# 07_RAM_PWR.net
KiCad netlist of a schematic drawn in Altium Designer
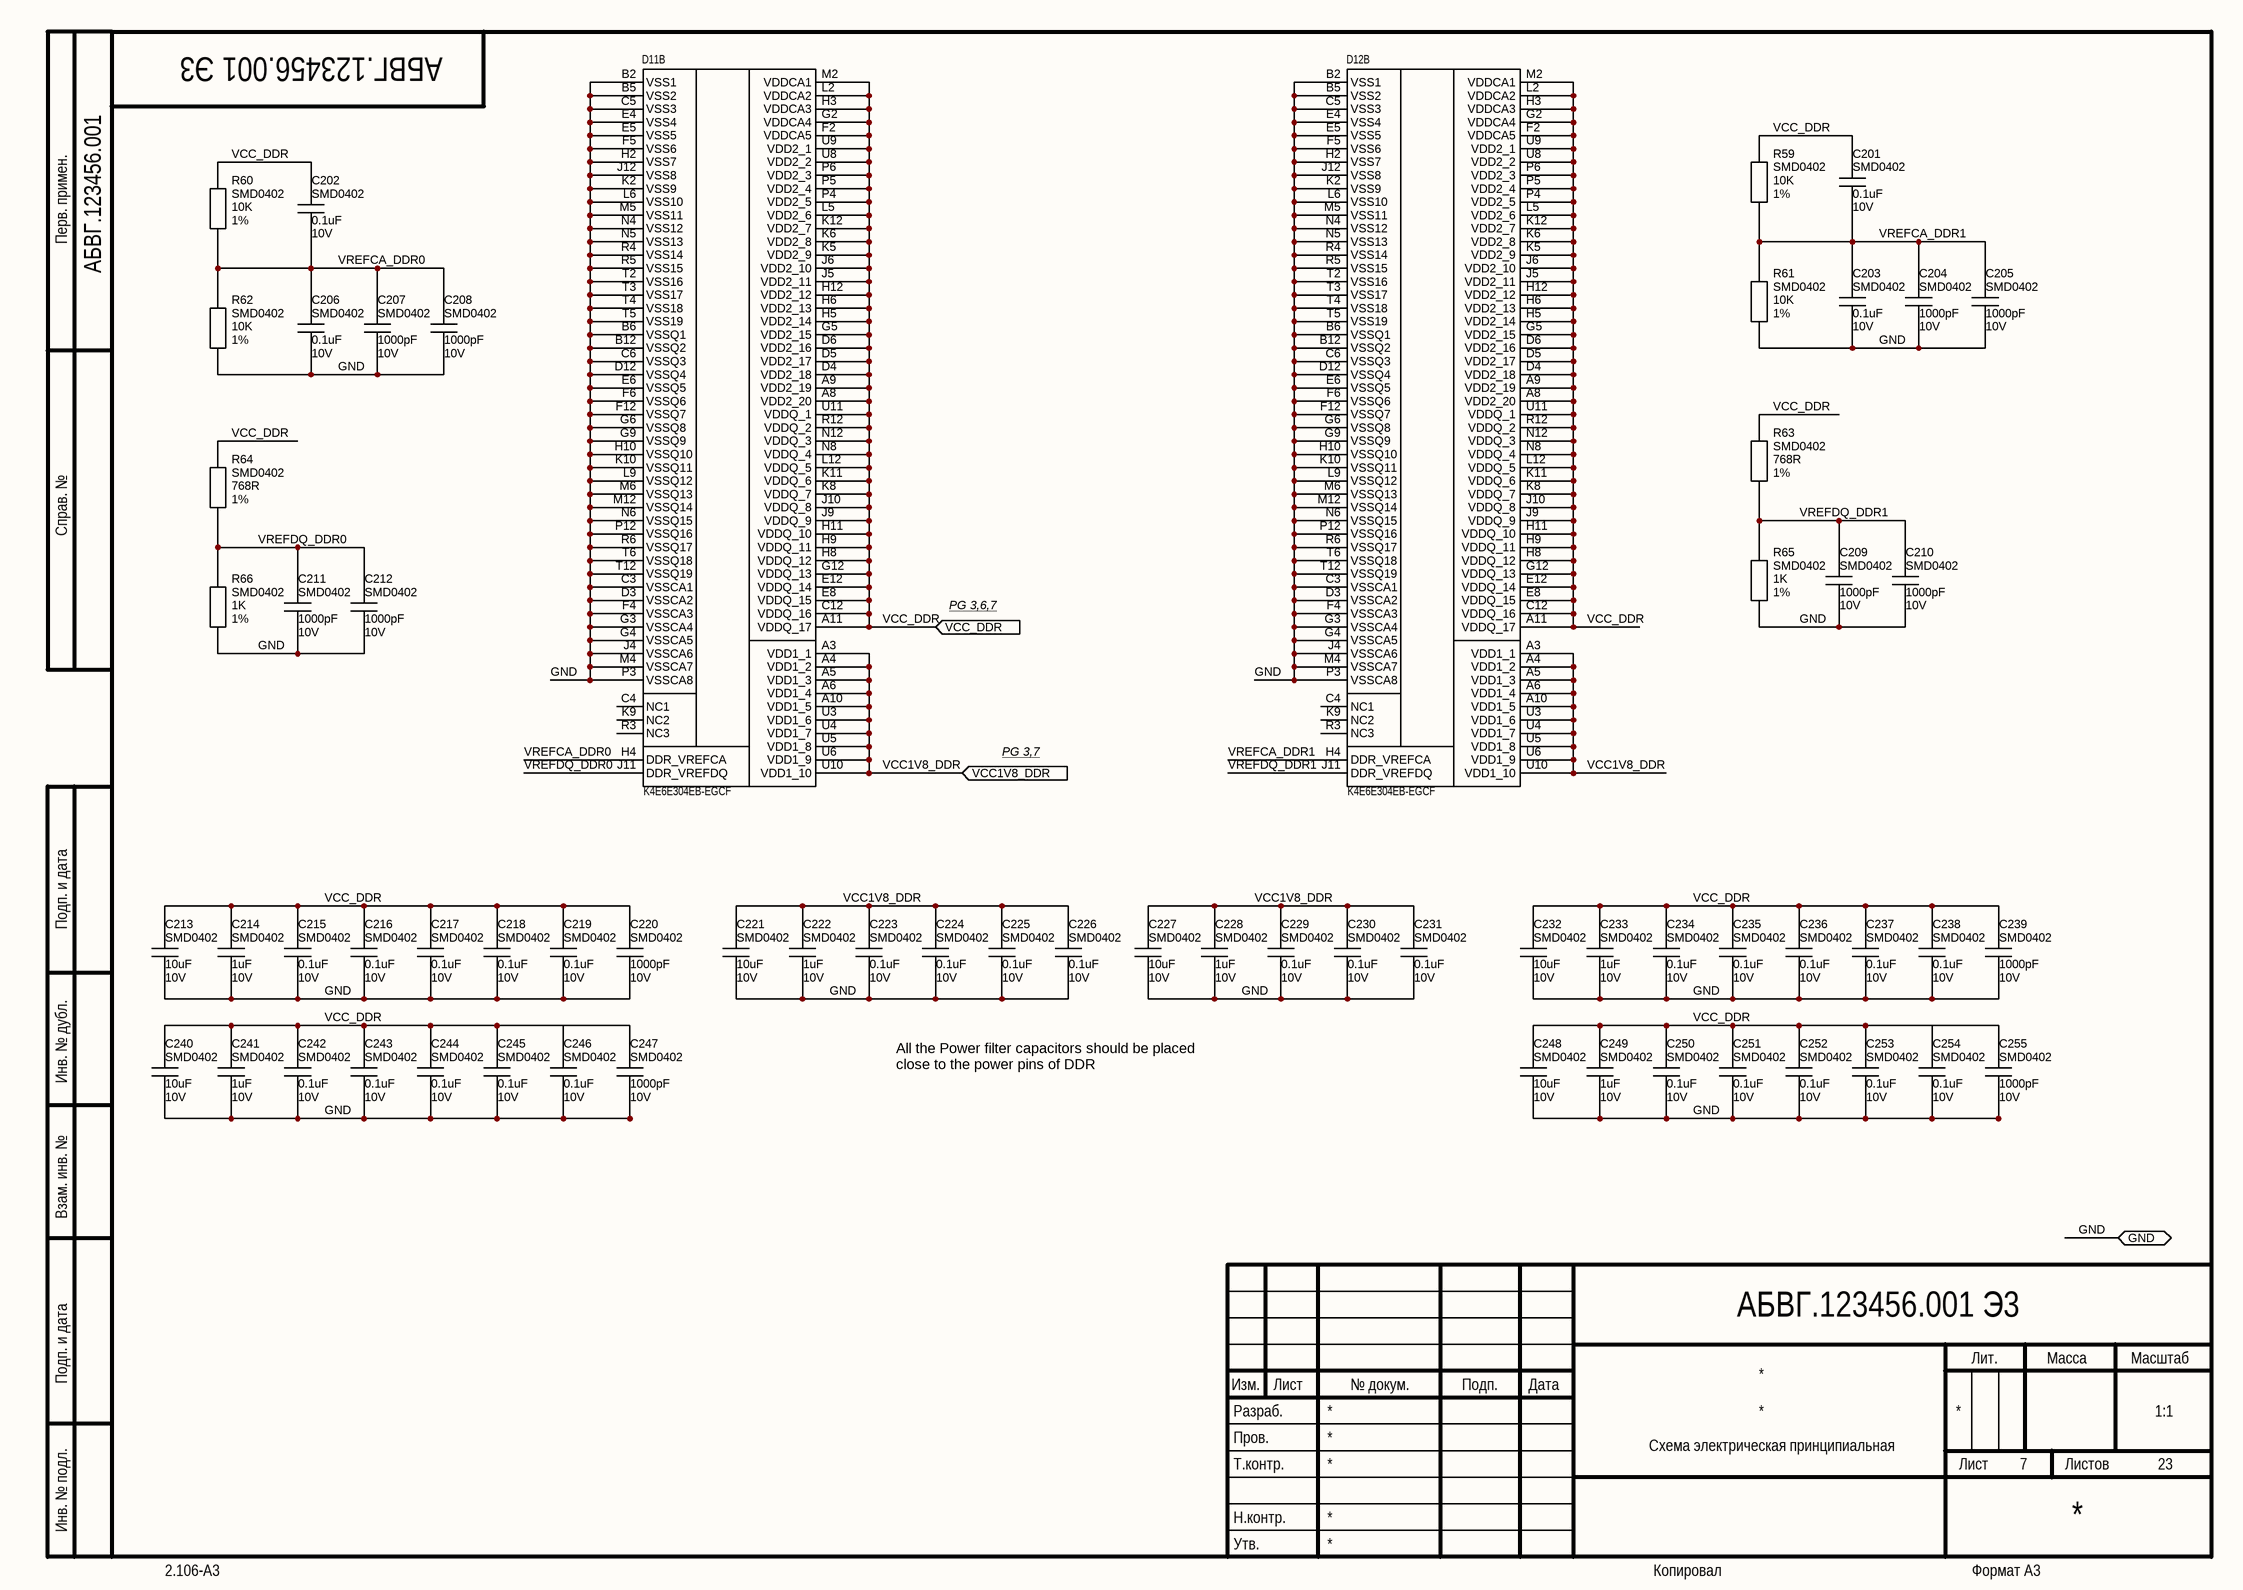
[diagram p0: 07 RAM_PWR.SchDoc]

(export (version "E")
  (design (tool "Eeschema 10.0.6"))
  (components
    (comp (ref "C201")
      (value "0.1uF")
      (footprint "Didur_PcbLib_1:CAP_SMD_0402_small")
      (fields
        (field (name "PACKAGE") "SMD0402")
        (field (name "PARTNUMBER") "CC0402KRX5R6BB104")
        (field (name "VOLTAGE") "10V")
      )
      (libsource (lib "Didur_SchLib_1") (part "Ceramic_Cap"))
    )
    (comp (ref "C202")
      (value "0.1uF")
      (footprint "Didur_PcbLib_1:CAP_SMD_0402_small")
      (fields
        (field (name "PACKAGE") "SMD0402")
        (field (name "PARTNUMBER") "CC0402KRX5R6BB104")
        (field (name "VOLTAGE") "10V")
      )
      (libsource (lib "Didur_SchLib_1") (part "Ceramic_Cap"))
    )
    (comp (ref "C203")
      (value "0.1uF")
      (footprint "Didur_PcbLib_1:CAP_SMD_0402_small")
      (fields
        (field (name "PACKAGE") "SMD0402")
        (field (name "PARTNUMBER") "CC0402KRX5R6BB104")
        (field (name "VOLTAGE") "10V")
      )
      (libsource (lib "Didur_SchLib_1") (part "Ceramic_Cap"))
    )
    (comp (ref "C204")
      (value "1000pF")
      (footprint "Didur_PcbLib_1:CAP_SMD_0402_small")
      (fields
        (field (name "PACKAGE") "SMD0402")
        (field (name "PARTNUMBER") "CC0402KRX7R9BB102")
        (field (name "VOLTAGE") "10V")
      )
      (libsource (lib "Didur_SchLib_1") (part "Ceramic_Cap"))
    )
    (comp (ref "C205")
      (value "1000pF")
      (footprint "Didur_PcbLib_1:CAP_SMD_0402_small")
      (fields
        (field (name "PACKAGE") "SMD0402")
        (field (name "PARTNUMBER") "CC0402KRX7R9BB102")
        (field (name "VOLTAGE") "10V")
      )
      (libsource (lib "Didur_SchLib_1") (part "Ceramic_Cap"))
    )
    (comp (ref "C206")
      (value "0.1uF")
      (footprint "Didur_PcbLib_1:CAP_SMD_0402_small")
      (fields
        (field (name "PACKAGE") "SMD0402")
        (field (name "PARTNUMBER") "CC0402KRX5R6BB104")
        (field (name "VOLTAGE") "10V")
      )
      (libsource (lib "Didur_SchLib_1") (part "Ceramic_Cap"))
    )
    (comp (ref "C207")
      (value "1000pF")
      (footprint "Didur_PcbLib_1:CAP_SMD_0402_small")
      (fields
        (field (name "PACKAGE") "SMD0402")
        (field (name "PARTNUMBER") "CC0402KRX7R9BB102")
        (field (name "VOLTAGE") "10V")
      )
      (libsource (lib "Didur_SchLib_1") (part "Ceramic_Cap"))
    )
    (comp (ref "C208")
      (value "1000pF")
      (footprint "Didur_PcbLib_1:CAP_SMD_0402_small")
      (fields
        (field (name "PACKAGE") "SMD0402")
        (field (name "PARTNUMBER") "CC0402KRX7R9BB102")
        (field (name "VOLTAGE") "10V")
      )
      (libsource (lib "Didur_SchLib_1") (part "Ceramic_Cap"))
    )
    (comp (ref "C209")
      (value "1000pF")
      (footprint "Didur_PcbLib_1:CAP_SMD_0402_small")
      (fields
        (field (name "PACKAGE") "SMD0402")
        (field (name "PARTNUMBER") "CC0402KRX7R9BB102")
        (field (name "VOLTAGE") "10V")
      )
      (libsource (lib "Didur_SchLib_1") (part "Ceramic_Cap"))
    )
    (comp (ref "C210")
      (value "1000pF")
      (footprint "Didur_PcbLib_1:CAP_SMD_0402_small")
      (fields
        (field (name "PACKAGE") "SMD0402")
        (field (name "PARTNUMBER") "CC0402KRX7R9BB102")
        (field (name "VOLTAGE") "10V")
      )
      (libsource (lib "Didur_SchLib_1") (part "Ceramic_Cap"))
    )
    (comp (ref "C211")
      (value "1000pF")
      (footprint "Didur_PcbLib_1:CAP_SMD_0402_small")
      (fields
        (field (name "PACKAGE") "SMD0402")
        (field (name "PARTNUMBER") "CC0402KRX7R9BB102")
        (field (name "VOLTAGE") "10V")
      )
      (libsource (lib "Didur_SchLib_1") (part "Ceramic_Cap"))
    )
    (comp (ref "C212")
      (value "1000pF")
      (footprint "Didur_PcbLib_1:CAP_SMD_0402_small")
      (fields
        (field (name "PACKAGE") "SMD0402")
        (field (name "PARTNUMBER") "CC0402KRX7R9BB102")
        (field (name "VOLTAGE") "10V")
      )
      (libsource (lib "Didur_SchLib_1") (part "Ceramic_Cap"))
    )
    (comp (ref "C213")
      (value "10uF")
      (footprint "Didur_PcbLib_1:CAP_SMD_0402_small")
      (fields
        (field (name "PACKAGE") "SMD0402")
        (field (name "PARTNUMBER") "CC0402MRX5R6BB106")
        (field (name "VOLTAGE") "10V")
      )
      (libsource (lib "Didur_SchLib_1") (part "Ceramic_Cap"))
    )
    (comp (ref "C214")
      (value "1uF")
      (footprint "Didur_PcbLib_1:CAP_SMD_0402_small")
      (fields
        (field (name "PACKAGE") "SMD0402")
        (field (name "PARTNUMBER") "CC0402KRX5R6BB105")
        (field (name "VOLTAGE") "10V")
      )
      (libsource (lib "Didur_SchLib_1") (part "Ceramic_Cap"))
    )
    (comp (ref "C215")
      (value "0.1uF")
      (footprint "Didur_PcbLib_1:CAP_SMD_0402_small")
      (fields
        (field (name "PACKAGE") "SMD0402")
        (field (name "PARTNUMBER") "CC0402KRX5R6BB104")
        (field (name "VOLTAGE") "10V")
      )
      (libsource (lib "Didur_SchLib_1") (part "Ceramic_Cap"))
    )
    (comp (ref "C216")
      (value "0.1uF")
      (footprint "Didur_PcbLib_1:CAP_SMD_0402_small")
      (fields
        (field (name "PACKAGE") "SMD0402")
        (field (name "PARTNUMBER") "CC0402KRX5R6BB104")
        (field (name "VOLTAGE") "10V")
      )
      (libsource (lib "Didur_SchLib_1") (part "Ceramic_Cap"))
    )
    (comp (ref "C217")
      (value "0.1uF")
      (footprint "Didur_PcbLib_1:CAP_SMD_0402_small")
      (fields
        (field (name "PACKAGE") "SMD0402")
        (field (name "PARTNUMBER") "CC0402KRX5R6BB104")
        (field (name "VOLTAGE") "10V")
      )
      (libsource (lib "Didur_SchLib_1") (part "Ceramic_Cap"))
    )
    (comp (ref "C218")
      (value "0.1uF")
      (footprint "Didur_PcbLib_1:CAP_SMD_0402_small")
      (fields
        (field (name "PACKAGE") "SMD0402")
        (field (name "PARTNUMBER") "CC0402KRX5R6BB104")
        (field (name "VOLTAGE") "10V")
      )
      (libsource (lib "Didur_SchLib_1") (part "Ceramic_Cap"))
    )
    (comp (ref "C219")
      (value "0.1uF")
      (footprint "Didur_PcbLib_1:CAP_SMD_0402_small")
      (fields
        (field (name "PACKAGE") "SMD0402")
        (field (name "PARTNUMBER") "CC0402KRX5R6BB104")
        (field (name "VOLTAGE") "10V")
      )
      (libsource (lib "Didur_SchLib_1") (part "Ceramic_Cap"))
    )
    (comp (ref "C220")
      (value "1000pF")
      (footprint "Didur_PcbLib_1:CAP_SMD_0402_small")
      (fields
        (field (name "PACKAGE") "SMD0402")
        (field (name "PARTNUMBER") "CC0402KRX7R9BB102")
        (field (name "VOLTAGE") "10V")
      )
      (libsource (lib "Didur_SchLib_1") (part "Ceramic_Cap"))
    )
    (comp (ref "C221")
      (value "10uF")
      (footprint "Didur_PcbLib_1:CAP_SMD_0402_small")
      (fields
        (field (name "PACKAGE") "SMD0402")
        (field (name "PARTNUMBER") "CC0402MRX5R6BB106")
        (field (name "VOLTAGE") "10V")
      )
      (libsource (lib "Didur_SchLib_1") (part "Ceramic_Cap"))
    )
    (comp (ref "C222")
      (value "1uF")
      (footprint "Didur_PcbLib_1:CAP_SMD_0402_small")
      (fields
        (field (name "PACKAGE") "SMD0402")
        (field (name "PARTNUMBER") "CC0402KRX5R6BB105")
        (field (name "VOLTAGE") "10V")
      )
      (libsource (lib "Didur_SchLib_1") (part "Ceramic_Cap"))
    )
    (comp (ref "C223")
      (value "0.1uF")
      (footprint "Didur_PcbLib_1:CAP_SMD_0402_small")
      (fields
        (field (name "PACKAGE") "SMD0402")
        (field (name "PARTNUMBER") "CC0402KRX5R6BB104")
        (field (name "VOLTAGE") "10V")
      )
      (libsource (lib "Didur_SchLib_1") (part "Ceramic_Cap"))
    )
    (comp (ref "C224")
      (value "0.1uF")
      (footprint "Didur_PcbLib_1:CAP_SMD_0402_small")
      (fields
        (field (name "PACKAGE") "SMD0402")
        (field (name "PARTNUMBER") "CC0402KRX5R6BB104")
        (field (name "VOLTAGE") "10V")
      )
      (libsource (lib "Didur_SchLib_1") (part "Ceramic_Cap"))
    )
    (comp (ref "C225")
      (value "0.1uF")
      (footprint "Didur_PcbLib_1:CAP_SMD_0402_small")
      (fields
        (field (name "PACKAGE") "SMD0402")
        (field (name "PARTNUMBER") "CC0402KRX5R6BB104")
        (field (name "VOLTAGE") "10V")
      )
      (libsource (lib "Didur_SchLib_1") (part "Ceramic_Cap"))
    )
    (comp (ref "C226")
      (value "0.1uF")
      (footprint "Didur_PcbLib_1:CAP_SMD_0402_small")
      (fields
        (field (name "PACKAGE") "SMD0402")
        (field (name "PARTNUMBER") "CC0402KRX5R6BB104")
        (field (name "VOLTAGE") "10V")
      )
      (libsource (lib "Didur_SchLib_1") (part "Ceramic_Cap"))
    )
    (comp (ref "C227")
      (value "10uF")
      (footprint "Didur_PcbLib_1:CAP_SMD_0402_small")
      (fields
        (field (name "PACKAGE") "SMD0402")
        (field (name "PARTNUMBER") "CC0402MRX5R6BB106")
        (field (name "VOLTAGE") "10V")
      )
      (libsource (lib "Didur_SchLib_1") (part "Ceramic_Cap"))
    )
    (comp (ref "C228")
      (value "1uF")
      (footprint "Didur_PcbLib_1:CAP_SMD_0402_small")
      (fields
        (field (name "PACKAGE") "SMD0402")
        (field (name "PARTNUMBER") "CC0402KRX5R6BB105")
        (field (name "VOLTAGE") "10V")
      )
      (libsource (lib "Didur_SchLib_1") (part "Ceramic_Cap"))
    )
    (comp (ref "C229")
      (value "0.1uF")
      (footprint "Didur_PcbLib_1:CAP_SMD_0402_small")
      (fields
        (field (name "PACKAGE") "SMD0402")
        (field (name "PARTNUMBER") "CC0402KRX5R6BB104")
        (field (name "VOLTAGE") "10V")
      )
      (libsource (lib "Didur_SchLib_1") (part "Ceramic_Cap"))
    )
    (comp (ref "C230")
      (value "0.1uF")
      (footprint "Didur_PcbLib_1:CAP_SMD_0402_small")
      (fields
        (field (name "PACKAGE") "SMD0402")
        (field (name "PARTNUMBER") "CC0402KRX5R6BB104")
        (field (name "VOLTAGE") "10V")
      )
      (libsource (lib "Didur_SchLib_1") (part "Ceramic_Cap"))
    )
    (comp (ref "C231")
      (value "0.1uF")
      (footprint "Didur_PcbLib_1:CAP_SMD_0402_small")
      (fields
        (field (name "PACKAGE") "SMD0402")
        (field (name "PARTNUMBER") "CC0402KRX5R6BB104")
        (field (name "VOLTAGE") "10V")
      )
      (libsource (lib "Didur_SchLib_1") (part "Ceramic_Cap"))
    )
    (comp (ref "C232")
      (value "10uF")
      (footprint "Didur_PcbLib_1:CAP_SMD_0402_small")
      (fields
        (field (name "PACKAGE") "SMD0402")
        (field (name "PARTNUMBER") "CC0402MRX5R6BB106")
        (field (name "VOLTAGE") "10V")
      )
      (libsource (lib "Didur_SchLib_1") (part "Ceramic_Cap"))
    )
    (comp (ref "C233")
      (value "1uF")
      (footprint "Didur_PcbLib_1:CAP_SMD_0402_small")
      (fields
        (field (name "PACKAGE") "SMD0402")
        (field (name "PARTNUMBER") "CC0402KRX5R6BB105")
        (field (name "VOLTAGE") "10V")
      )
      (libsource (lib "Didur_SchLib_1") (part "Ceramic_Cap"))
    )
    (comp (ref "C234")
      (value "0.1uF")
      (footprint "Didur_PcbLib_1:CAP_SMD_0402_small")
      (fields
        (field (name "PACKAGE") "SMD0402")
        (field (name "PARTNUMBER") "CC0402KRX5R6BB104")
        (field (name "VOLTAGE") "10V")
      )
      (libsource (lib "Didur_SchLib_1") (part "Ceramic_Cap"))
    )
    (comp (ref "C235")
      (value "0.1uF")
      (footprint "Didur_PcbLib_1:CAP_SMD_0402_small")
      (fields
        (field (name "PACKAGE") "SMD0402")
        (field (name "PARTNUMBER") "CC0402KRX5R6BB104")
        (field (name "VOLTAGE") "10V")
      )
      (libsource (lib "Didur_SchLib_1") (part "Ceramic_Cap"))
    )
    (comp (ref "C236")
      (value "0.1uF")
      (footprint "Didur_PcbLib_1:CAP_SMD_0402_small")
      (fields
        (field (name "PACKAGE") "SMD0402")
        (field (name "PARTNUMBER") "CC0402KRX5R6BB104")
        (field (name "VOLTAGE") "10V")
      )
      (libsource (lib "Didur_SchLib_1") (part "Ceramic_Cap"))
    )
    (comp (ref "C237")
      (value "0.1uF")
      (footprint "Didur_PcbLib_1:CAP_SMD_0402_small")
      (fields
        (field (name "PACKAGE") "SMD0402")
        (field (name "PARTNUMBER") "CC0402KRX5R6BB104")
        (field (name "VOLTAGE") "10V")
      )
      (libsource (lib "Didur_SchLib_1") (part "Ceramic_Cap"))
    )
    (comp (ref "C238")
      (value "0.1uF")
      (footprint "Didur_PcbLib_1:CAP_SMD_0402_small")
      (fields
        (field (name "PACKAGE") "SMD0402")
        (field (name "PARTNUMBER") "CC0402KRX5R6BB104")
        (field (name "VOLTAGE") "10V")
      )
      (libsource (lib "Didur_SchLib_1") (part "Ceramic_Cap"))
    )
    (comp (ref "C239")
      (value "1000pF")
      (footprint "Didur_PcbLib_1:CAP_SMD_0402_small")
      (fields
        (field (name "PACKAGE") "SMD0402")
        (field (name "PARTNUMBER") "CC0402KRX7R9BB102")
        (field (name "VOLTAGE") "10V")
      )
      (libsource (lib "Didur_SchLib_1") (part "Ceramic_Cap"))
    )
    (comp (ref "C240")
      (value "10uF")
      (footprint "Didur_PcbLib_1:CAP_SMD_0402_small")
      (fields
        (field (name "PACKAGE") "SMD0402")
        (field (name "PARTNUMBER") "CC0402MRX5R6BB106")
        (field (name "VOLTAGE") "10V")
      )
      (libsource (lib "Didur_SchLib_1") (part "Ceramic_Cap"))
    )
    (comp (ref "C241")
      (value "1uF")
      (footprint "Didur_PcbLib_1:CAP_SMD_0402_small")
      (fields
        (field (name "PACKAGE") "SMD0402")
        (field (name "PARTNUMBER") "CC0402KRX5R6BB105")
        (field (name "VOLTAGE") "10V")
      )
      (libsource (lib "Didur_SchLib_1") (part "Ceramic_Cap"))
    )
    (comp (ref "C242")
      (value "0.1uF")
      (footprint "Didur_PcbLib_1:CAP_SMD_0402_small")
      (fields
        (field (name "PACKAGE") "SMD0402")
        (field (name "PARTNUMBER") "CC0402KRX5R6BB104")
        (field (name "VOLTAGE") "10V")
      )
      (libsource (lib "Didur_SchLib_1") (part "Ceramic_Cap"))
    )
    (comp (ref "C243")
      (value "0.1uF")
      (footprint "Didur_PcbLib_1:CAP_SMD_0402_small")
      (fields
        (field (name "PACKAGE") "SMD0402")
        (field (name "PARTNUMBER") "CC0402KRX5R6BB104")
        (field (name "VOLTAGE") "10V")
      )
      (libsource (lib "Didur_SchLib_1") (part "Ceramic_Cap"))
    )
    (comp (ref "C244")
      (value "0.1uF")
      (footprint "Didur_PcbLib_1:CAP_SMD_0402_small")
      (fields
        (field (name "PACKAGE") "SMD0402")
        (field (name "PARTNUMBER") "CC0402KRX5R6BB104")
        (field (name "VOLTAGE") "10V")
      )
      (libsource (lib "Didur_SchLib_1") (part "Ceramic_Cap"))
    )
    (comp (ref "C245")
      (value "0.1uF")
      (footprint "Didur_PcbLib_1:CAP_SMD_0402_small")
      (fields
        (field (name "PACKAGE") "SMD0402")
        (field (name "PARTNUMBER") "CC0402KRX5R6BB104")
        (field (name "VOLTAGE") "10V")
      )
      (libsource (lib "Didur_SchLib_1") (part "Ceramic_Cap"))
    )
    (comp (ref "C246")
      (value "0.1uF")
      (footprint "Didur_PcbLib_1:CAP_SMD_0402_small")
      (fields
        (field (name "PACKAGE") "SMD0402")
        (field (name "PARTNUMBER") "CC0402KRX5R6BB104")
        (field (name "VOLTAGE") "10V")
      )
      (libsource (lib "Didur_SchLib_1") (part "Ceramic_Cap"))
    )
    (comp (ref "C247")
      (value "1000pF")
      (footprint "Didur_PcbLib_1:CAP_SMD_0402_small")
      (fields
        (field (name "PACKAGE") "SMD0402")
        (field (name "PARTNUMBER") "CC0402KRX7R9BB102")
        (field (name "VOLTAGE") "10V")
      )
      (libsource (lib "Didur_SchLib_1") (part "Ceramic_Cap"))
    )
    (comp (ref "C248")
      (value "10uF")
      (footprint "Didur_PcbLib_1:CAP_SMD_0402_small")
      (fields
        (field (name "PACKAGE") "SMD0402")
        (field (name "PARTNUMBER") "CC0402MRX5R6BB106")
        (field (name "VOLTAGE") "10V")
      )
      (libsource (lib "Didur_SchLib_1") (part "Ceramic_Cap"))
    )
    (comp (ref "C249")
      (value "1uF")
      (footprint "Didur_PcbLib_1:CAP_SMD_0402_small")
      (fields
        (field (name "PACKAGE") "SMD0402")
        (field (name "PARTNUMBER") "CC0402KRX5R6BB105")
        (field (name "VOLTAGE") "10V")
      )
      (libsource (lib "Didur_SchLib_1") (part "Ceramic_Cap"))
    )
    (comp (ref "C250")
      (value "0.1uF")
      (footprint "Didur_PcbLib_1:CAP_SMD_0402_small")
      (fields
        (field (name "PACKAGE") "SMD0402")
        (field (name "PARTNUMBER") "CC0402KRX5R6BB104")
        (field (name "VOLTAGE") "10V")
      )
      (libsource (lib "Didur_SchLib_1") (part "Ceramic_Cap"))
    )
    (comp (ref "C251")
      (value "0.1uF")
      (footprint "Didur_PcbLib_1:CAP_SMD_0402_small")
      (fields
        (field (name "PACKAGE") "SMD0402")
        (field (name "PARTNUMBER") "CC0402KRX5R6BB104")
        (field (name "VOLTAGE") "10V")
      )
      (libsource (lib "Didur_SchLib_1") (part "Ceramic_Cap"))
    )
    (comp (ref "C252")
      (value "0.1uF")
      (footprint "Didur_PcbLib_1:CAP_SMD_0402_small")
      (fields
        (field (name "PACKAGE") "SMD0402")
        (field (name "PARTNUMBER") "CC0402KRX5R6BB104")
        (field (name "VOLTAGE") "10V")
      )
      (libsource (lib "Didur_SchLib_1") (part "Ceramic_Cap"))
    )
    (comp (ref "C253")
      (value "0.1uF")
      (footprint "Didur_PcbLib_1:CAP_SMD_0402_small")
      (fields
        (field (name "PACKAGE") "SMD0402")
        (field (name "PARTNUMBER") "CC0402KRX5R6BB104")
        (field (name "VOLTAGE") "10V")
      )
      (libsource (lib "Didur_SchLib_1") (part "Ceramic_Cap"))
    )
    (comp (ref "C254")
      (value "0.1uF")
      (footprint "Didur_PcbLib_1:CAP_SMD_0402_small")
      (fields
        (field (name "PACKAGE") "SMD0402")
        (field (name "PARTNUMBER") "CC0402KRX5R6BB104")
        (field (name "VOLTAGE") "10V")
      )
      (libsource (lib "Didur_SchLib_1") (part "Ceramic_Cap"))
    )
    (comp (ref "C255")
      (value "1000pF")
      (footprint "Didur_PcbLib_1:CAP_SMD_0402_small")
      (fields
        (field (name "PACKAGE") "SMD0402")
        (field (name "PARTNUMBER") "CC0402KRX7R9BB102")
        (field (name "VOLTAGE") "10V")
      )
      (libsource (lib "Didur_SchLib_1") (part "Ceramic_Cap"))
    )
    (comp (ref "D11")
      (value "K4E6E304EB-EGCF")
      (footprint "Didur_PcbLib_1:FBGA178_13R00X11R50X1R20")
      (libsource (lib "Didur_SchLib_1") (part "K4E8E304EE-EGCE"))
    )
    (comp (ref "D12")
      (value "K4E6E304EB-EGCF")
      (footprint "Didur_PcbLib_1:FBGA178_13R00X11R50X1R20")
      (libsource (lib "Didur_SchLib_1") (part "K4E8E304EE-EGCE"))
    )
    (comp (ref "R59")
      (value "10K")
      (footprint "Didur_PcbLib_1:RES_SMD_0402_SMALL")
      (fields
        (field (name "PACKAGE") "SMD0402")
        (field (name "PARTNUMBER") "RC0402FR-0710KL")
        (field (name "TOLERANCE") "1%")
      )
      (libsource (lib "") (part "Chip_Res_1"))
    )
    (comp (ref "R60")
      (value "10K")
      (footprint "Didur_PcbLib_1:RES_SMD_0402_SMALL")
      (fields
        (field (name "PACKAGE") "SMD0402")
        (field (name "PARTNUMBER") "RC0402FR-0710KL")
        (field (name "TOLERANCE") "1%")
      )
      (libsource (lib "") (part "Chip_Res_1"))
    )
    (comp (ref "R61")
      (value "10K")
      (footprint "Didur_PcbLib_1:RES_SMD_0402_SMALL")
      (fields
        (field (name "PACKAGE") "SMD0402")
        (field (name "PARTNUMBER") "RC0402FR-0710KL")
        (field (name "TOLERANCE") "1%")
      )
      (libsource (lib "") (part "Chip_Res_1"))
    )
    (comp (ref "R62")
      (value "10K")
      (footprint "Didur_PcbLib_1:RES_SMD_0402_SMALL")
      (fields
        (field (name "PACKAGE") "SMD0402")
        (field (name "PARTNUMBER") "RC0402FR-0710KL")
        (field (name "TOLERANCE") "1%")
      )
      (libsource (lib "") (part "Chip_Res_1"))
    )
    (comp (ref "R63")
      (value "768R")
      (footprint "Didur_PcbLib_1:RES_SMD_0402_SMALL")
      (fields
        (field (name "PACKAGE") "SMD0402")
        (field (name "PARTNUMBER") "RC0402FR-07768RL")
        (field (name "TOLERANCE") "1%")
      )
      (libsource (lib "") (part "Chip_Res_1"))
    )
    (comp (ref "R64")
      (value "768R")
      (footprint "Didur_PcbLib_1:RES_SMD_0402_SMALL")
      (fields
        (field (name "PACKAGE") "SMD0402")
        (field (name "PARTNUMBER") "RC0402FR-07768RL")
        (field (name "TOLERANCE") "1%")
      )
      (libsource (lib "") (part "Chip_Res_1"))
    )
    (comp (ref "R65")
      (value "1K")
      (footprint "Didur_PcbLib_1:RES_SMD_0402_SMALL")
      (fields
        (field (name "PACKAGE") "SMD0402")
        (field (name "PARTNUMBER") "RC0402FR-071KL")
        (field (name "TOLERANCE") "1%")
      )
      (libsource (lib "Didur_SchLib_1") (part "Chip_Res"))
    )
    (comp (ref "R66")
      (value "1K")
      (footprint "Didur_PcbLib_1:RES_SMD_0402_SMALL")
      (fields
        (field (name "PACKAGE") "SMD0402")
        (field (name "PARTNUMBER") "RC0402FR-071KL")
        (field (name "TOLERANCE") "1%")
      )
      (libsource (lib "Didur_SchLib_1") (part "Chip_Res"))
    )
  )
  (nets
    (net (code "1") (name "/GND") (class "Default")
      (node (ref "C203") (pin "2") (pinfunction "2_2") (pintype "power_in"))
      (node (ref "C204") (pin "1") (pinfunction "1_1") (pintype "power_in"))
      (node (ref "C205") (pin "1") (pinfunction "1_1") (pintype "power_in"))
      (node (ref "C206") (pin "2") (pinfunction "2_2") (pintype "power_in"))
      (node (ref "C207") (pin "1") (pinfunction "1_1") (pintype "power_in"))
      (node (ref "C208") (pin "1") (pinfunction "1_1") (pintype "power_in"))
      (node (ref "C209") (pin "1") (pinfunction "1_1") (pintype "power_in"))
      (node (ref "C210") (pin "1") (pinfunction "1_1") (pintype "power_in"))
      (node (ref "C211") (pin "1") (pinfunction "1_1") (pintype "power_in"))
      (node (ref "C212") (pin "1") (pinfunction "1_1") (pintype "power_in"))
      (node (ref "C213") (pin "2") (pinfunction "2_2") (pintype "power_in"))
      (node (ref "C214") (pin "2") (pinfunction "2_2") (pintype "power_in"))
      (node (ref "C215") (pin "2") (pinfunction "2_2") (pintype "power_in"))
      (node (ref "C216") (pin "2") (pinfunction "2_2") (pintype "power_in"))
      (node (ref "C217") (pin "2") (pinfunction "2_2") (pintype "power_in"))
      (node (ref "C218") (pin "2") (pinfunction "2_2") (pintype "power_in"))
      (node (ref "C219") (pin "2") (pinfunction "2_2") (pintype "power_in"))
      (node (ref "C220") (pin "1") (pinfunction "1_1") (pintype "power_in"))
      (node (ref "C221") (pin "2") (pinfunction "2_2") (pintype "power_in"))
      (node (ref "C222") (pin "2") (pinfunction "2_2") (pintype "power_in"))
      (node (ref "C223") (pin "2") (pinfunction "2_2") (pintype "power_in"))
      (node (ref "C224") (pin "2") (pinfunction "2_2") (pintype "power_in"))
      (node (ref "C225") (pin "2") (pinfunction "2_2") (pintype "power_in"))
      (node (ref "C226") (pin "2") (pinfunction "2_2") (pintype "power_in"))
      (node (ref "C227") (pin "2") (pinfunction "2_2") (pintype "power_in"))
      (node (ref "C228") (pin "2") (pinfunction "2_2") (pintype "power_in"))
      (node (ref "C229") (pin "2") (pinfunction "2_2") (pintype "power_in"))
      (node (ref "C230") (pin "2") (pinfunction "2_2") (pintype "power_in"))
      (node (ref "C231") (pin "2") (pinfunction "2_2") (pintype "power_in"))
      (node (ref "C232") (pin "2") (pinfunction "2_2") (pintype "power_in"))
      (node (ref "C233") (pin "2") (pinfunction "2_2") (pintype "power_in"))
      (node (ref "C234") (pin "2") (pinfunction "2_2") (pintype "power_in"))
      (node (ref "C235") (pin "2") (pinfunction "2_2") (pintype "power_in"))
      (node (ref "C236") (pin "2") (pinfunction "2_2") (pintype "power_in"))
      (node (ref "C237") (pin "2") (pinfunction "2_2") (pintype "power_in"))
      (node (ref "C238") (pin "2") (pinfunction "2_2") (pintype "power_in"))
      (node (ref "C239") (pin "1") (pinfunction "1_1") (pintype "power_in"))
      (node (ref "C240") (pin "2") (pinfunction "2_2") (pintype "power_in"))
      (node (ref "C241") (pin "2") (pinfunction "2_2") (pintype "power_in"))
      (node (ref "C242") (pin "2") (pinfunction "2_2") (pintype "power_in"))
      (node (ref "C243") (pin "2") (pinfunction "2_2") (pintype "power_in"))
      (node (ref "C244") (pin "2") (pinfunction "2_2") (pintype "power_in"))
      (node (ref "C245") (pin "2") (pinfunction "2_2") (pintype "power_in"))
      (node (ref "C246") (pin "2") (pinfunction "2_2") (pintype "power_in"))
      (node (ref "C247") (pin "1") (pinfunction "1_1") (pintype "power_in"))
      (node (ref "C248") (pin "2") (pinfunction "2_2") (pintype "power_in"))
      (node (ref "C249") (pin "2") (pinfunction "2_2") (pintype "power_in"))
      (node (ref "C250") (pin "2") (pinfunction "2_2") (pintype "power_in"))
      (node (ref "C251") (pin "2") (pinfunction "2_2") (pintype "power_in"))
      (node (ref "C252") (pin "2") (pinfunction "2_2") (pintype "power_in"))
      (node (ref "C253") (pin "2") (pinfunction "2_2") (pintype "power_in"))
      (node (ref "C254") (pin "2") (pinfunction "2_2") (pintype "power_in"))
      (node (ref "C255") (pin "1") (pinfunction "1_1") (pintype "power_in"))
      (node (ref "D11") (pin "B12") (pinfunction "VSSQ2_B12") (pintype "passive"))
      (node (ref "D11") (pin "B2") (pinfunction "VSS1_B2") (pintype "passive"))
      (node (ref "D11") (pin "B5") (pinfunction "VSS2_B5") (pintype "passive"))
      (node (ref "D11") (pin "B6") (pinfunction "VSSQ1_B6") (pintype "passive"))
      (node (ref "D11") (pin "C3") (pinfunction "VSSCA1_C3") (pintype "passive"))
      (node (ref "D11") (pin "C5") (pinfunction "VSS3_C5") (pintype "passive"))
      (node (ref "D11") (pin "C6") (pinfunction "VSSQ3_C6") (pintype "passive"))
      (node (ref "D11") (pin "D12") (pinfunction "VSSQ4_D12") (pintype "passive"))
      (node (ref "D11") (pin "D3") (pinfunction "VSSCA2_D3") (pintype "passive"))
      (node (ref "D11") (pin "E4") (pinfunction "VSS4_E4") (pintype "passive"))
      (node (ref "D11") (pin "E5") (pinfunction "VSS5_E5") (pintype "passive"))
      (node (ref "D11") (pin "E6") (pinfunction "VSSQ5_E6") (pintype "passive"))
      (node (ref "D11") (pin "F12") (pinfunction "VSSQ7_F12") (pintype "passive"))
      (node (ref "D11") (pin "F4") (pinfunction "VSSCA3_F4") (pintype "passive"))
      (node (ref "D11") (pin "F5") (pinfunction "VSS6_F5") (pintype "passive"))
      (node (ref "D11") (pin "F6") (pinfunction "VSSQ6_F6") (pintype "passive"))
      (node (ref "D11") (pin "G3") (pinfunction "VSSCA4_G3") (pintype "passive"))
      (node (ref "D11") (pin "G4") (pinfunction "VSSCA5_G4") (pintype "passive"))
      (node (ref "D11") (pin "G6") (pinfunction "VSSQ8_G6") (pintype "passive"))
      (node (ref "D11") (pin "G9") (pinfunction "VSSQ9_G9") (pintype "passive"))
      (node (ref "D11") (pin "H10") (pinfunction "VSSQ10_H10") (pintype "passive"))
      (node (ref "D11") (pin "H2") (pinfunction "VSS7_H2") (pintype "passive"))
      (node (ref "D11") (pin "J12") (pinfunction "VSS8_J12") (pintype "passive"))
      (node (ref "D11") (pin "J4") (pinfunction "VSSCA6_J4") (pintype "passive"))
      (node (ref "D11") (pin "K10") (pinfunction "VSSQ11_K10") (pintype "passive"))
      (node (ref "D11") (pin "K2") (pinfunction "VSS9_K2") (pintype "passive"))
      (node (ref "D11") (pin "L6") (pinfunction "VSS10_L6") (pintype "passive"))
      (node (ref "D11") (pin "L9") (pinfunction "VSSQ12_L9") (pintype "passive"))
      (node (ref "D11") (pin "M12") (pinfunction "VSSQ14_M12") (pintype "passive"))
      (node (ref "D11") (pin "M4") (pinfunction "VSSCA7_M4") (pintype "passive"))
      (node (ref "D11") (pin "M5") (pinfunction "VSS11_M5") (pintype "passive"))
      (node (ref "D11") (pin "M6") (pinfunction "VSSQ13_M6") (pintype "passive"))
      (node (ref "D11") (pin "N4") (pinfunction "VSS12_N4") (pintype "passive"))
      (node (ref "D11") (pin "N5") (pinfunction "VSS13_N5") (pintype "passive"))
      (node (ref "D11") (pin "N6") (pinfunction "VSSQ15_N6") (pintype "passive"))
      (node (ref "D11") (pin "P12") (pinfunction "VSSQ16_P12") (pintype "passive"))
      (node (ref "D11") (pin "P3") (pinfunction "VSSCA8_P3") (pintype "passive"))
      (node (ref "D11") (pin "R4") (pinfunction "VSS14_R4") (pintype "passive"))
      (node (ref "D11") (pin "R5") (pinfunction "VSS15_R5") (pintype "passive"))
      (node (ref "D11") (pin "R6") (pinfunction "VSSQ17_R6") (pintype "passive"))
      (node (ref "D11") (pin "T12") (pinfunction "VSSQ19_T12") (pintype "passive"))
      (node (ref "D11") (pin "T2") (pinfunction "VSS16_T2") (pintype "passive"))
      (node (ref "D11") (pin "T3") (pinfunction "VSS17_T3") (pintype "passive"))
      (node (ref "D11") (pin "T4") (pinfunction "VSS18_T4") (pintype "passive"))
      (node (ref "D11") (pin "T5") (pinfunction "VSS19_T5") (pintype "passive"))
      (node (ref "D11") (pin "T6") (pinfunction "VSSQ18_T6") (pintype "passive"))
      (node (ref "D12") (pin "B12") (pinfunction "VSSQ2_B12") (pintype "passive"))
      (node (ref "D12") (pin "B2") (pinfunction "VSS1_B2") (pintype "passive"))
      (node (ref "D12") (pin "B5") (pinfunction "VSS2_B5") (pintype "passive"))
      (node (ref "D12") (pin "B6") (pinfunction "VSSQ1_B6") (pintype "passive"))
      (node (ref "D12") (pin "C3") (pinfunction "VSSCA1_C3") (pintype "passive"))
      (node (ref "D12") (pin "C5") (pinfunction "VSS3_C5") (pintype "passive"))
      (node (ref "D12") (pin "C6") (pinfunction "VSSQ3_C6") (pintype "passive"))
      (node (ref "D12") (pin "D12") (pinfunction "VSSQ4_D12") (pintype "passive"))
      (node (ref "D12") (pin "D3") (pinfunction "VSSCA2_D3") (pintype "passive"))
      (node (ref "D12") (pin "E4") (pinfunction "VSS4_E4") (pintype "passive"))
      (node (ref "D12") (pin "E5") (pinfunction "VSS5_E5") (pintype "passive"))
      (node (ref "D12") (pin "E6") (pinfunction "VSSQ5_E6") (pintype "passive"))
      (node (ref "D12") (pin "F12") (pinfunction "VSSQ7_F12") (pintype "passive"))
      (node (ref "D12") (pin "F4") (pinfunction "VSSCA3_F4") (pintype "passive"))
      (node (ref "D12") (pin "F5") (pinfunction "VSS6_F5") (pintype "passive"))
      (node (ref "D12") (pin "F6") (pinfunction "VSSQ6_F6") (pintype "passive"))
      (node (ref "D12") (pin "G3") (pinfunction "VSSCA4_G3") (pintype "passive"))
      (node (ref "D12") (pin "G4") (pinfunction "VSSCA5_G4") (pintype "passive"))
      (node (ref "D12") (pin "G6") (pinfunction "VSSQ8_G6") (pintype "passive"))
      (node (ref "D12") (pin "G9") (pinfunction "VSSQ9_G9") (pintype "passive"))
      (node (ref "D12") (pin "H10") (pinfunction "VSSQ10_H10") (pintype "passive"))
      (node (ref "D12") (pin "H2") (pinfunction "VSS7_H2") (pintype "passive"))
      (node (ref "D12") (pin "J12") (pinfunction "VSS8_J12") (pintype "passive"))
      (node (ref "D12") (pin "J4") (pinfunction "VSSCA6_J4") (pintype "passive"))
      (node (ref "D12") (pin "K10") (pinfunction "VSSQ11_K10") (pintype "passive"))
      (node (ref "D12") (pin "K2") (pinfunction "VSS9_K2") (pintype "passive"))
      (node (ref "D12") (pin "L6") (pinfunction "VSS10_L6") (pintype "passive"))
      (node (ref "D12") (pin "L9") (pinfunction "VSSQ12_L9") (pintype "passive"))
      (node (ref "D12") (pin "M12") (pinfunction "VSSQ14_M12") (pintype "passive"))
      (node (ref "D12") (pin "M4") (pinfunction "VSSCA7_M4") (pintype "passive"))
      (node (ref "D12") (pin "M5") (pinfunction "VSS11_M5") (pintype "passive"))
      (node (ref "D12") (pin "M6") (pinfunction "VSSQ13_M6") (pintype "passive"))
      (node (ref "D12") (pin "N4") (pinfunction "VSS12_N4") (pintype "passive"))
      (node (ref "D12") (pin "N5") (pinfunction "VSS13_N5") (pintype "passive"))
      (node (ref "D12") (pin "N6") (pinfunction "VSSQ15_N6") (pintype "passive"))
      (node (ref "D12") (pin "P12") (pinfunction "VSSQ16_P12") (pintype "passive"))
      (node (ref "D12") (pin "P3") (pinfunction "VSSCA8_P3") (pintype "passive"))
      (node (ref "D12") (pin "R4") (pinfunction "VSS14_R4") (pintype "passive"))
      (node (ref "D12") (pin "R5") (pinfunction "VSS15_R5") (pintype "passive"))
      (node (ref "D12") (pin "R6") (pinfunction "VSSQ17_R6") (pintype "passive"))
      (node (ref "D12") (pin "T12") (pinfunction "VSSQ19_T12") (pintype "passive"))
      (node (ref "D12") (pin "T2") (pinfunction "VSS16_T2") (pintype "passive"))
      (node (ref "D12") (pin "T3") (pinfunction "VSS17_T3") (pintype "passive"))
      (node (ref "D12") (pin "T4") (pinfunction "VSS18_T4") (pintype "passive"))
      (node (ref "D12") (pin "T5") (pinfunction "VSS19_T5") (pintype "passive"))
      (node (ref "D12") (pin "T6") (pinfunction "VSSQ18_T6") (pintype "passive"))
      (node (ref "R61") (pin "1") (pinfunction "1_1") (pintype "passive"))
      (node (ref "R62") (pin "1") (pinfunction "1_1") (pintype "passive"))
      (node (ref "R65") (pin "1") (pinfunction "1_1") (pintype "passive"))
      (node (ref "R66") (pin "1") (pinfunction "1_1") (pintype "passive"))
    )
    (net (code "2") (name "/VCC1V8_DDR") (class "Default")
      (node (ref "C221") (pin "1") (pinfunction "1_1") (pintype "power_in"))
      (node (ref "C222") (pin "1") (pinfunction "1_1") (pintype "power_in"))
      (node (ref "C223") (pin "1") (pinfunction "1_1") (pintype "power_in"))
      (node (ref "C224") (pin "1") (pinfunction "1_1") (pintype "power_in"))
      (node (ref "C225") (pin "1") (pinfunction "1_1") (pintype "power_in"))
      (node (ref "C226") (pin "1") (pinfunction "1_1") (pintype "power_in"))
      (node (ref "C227") (pin "1") (pinfunction "1_1") (pintype "power_in"))
      (node (ref "C228") (pin "1") (pinfunction "1_1") (pintype "power_in"))
      (node (ref "C229") (pin "1") (pinfunction "1_1") (pintype "power_in"))
      (node (ref "C230") (pin "1") (pinfunction "1_1") (pintype "power_in"))
      (node (ref "C231") (pin "1") (pinfunction "1_1") (pintype "power_in"))
      (node (ref "D11") (pin "A10") (pinfunction "VDD1_5_A10") (pintype "passive"))
      (node (ref "D11") (pin "A3") (pinfunction "VDD1_1_A3") (pintype "passive"))
      (node (ref "D11") (pin "A4") (pinfunction "VDD1_2_A4") (pintype "passive"))
      (node (ref "D11") (pin "A5") (pinfunction "VDD1_3_A5") (pintype "passive"))
      (node (ref "D11") (pin "A6") (pinfunction "VDD1_4_A6") (pintype "passive"))
      (node (ref "D11") (pin "U10") (pinfunction "VDD1_10_U10") (pintype "passive"))
      (node (ref "D11") (pin "U3") (pinfunction "VDD1_6_U3") (pintype "passive"))
      (node (ref "D11") (pin "U4") (pinfunction "VDD1_7_U4") (pintype "passive"))
      (node (ref "D11") (pin "U5") (pinfunction "VDD1_8_U5") (pintype "passive"))
      (node (ref "D11") (pin "U6") (pinfunction "VDD1_9_U6") (pintype "passive"))
      (node (ref "D12") (pin "A10") (pinfunction "VDD1_5_A10") (pintype "passive"))
      (node (ref "D12") (pin "A3") (pinfunction "VDD1_1_A3") (pintype "passive"))
      (node (ref "D12") (pin "A4") (pinfunction "VDD1_2_A4") (pintype "passive"))
      (node (ref "D12") (pin "A5") (pinfunction "VDD1_3_A5") (pintype "passive"))
      (node (ref "D12") (pin "A6") (pinfunction "VDD1_4_A6") (pintype "passive"))
      (node (ref "D12") (pin "U10") (pinfunction "VDD1_10_U10") (pintype "passive"))
      (node (ref "D12") (pin "U3") (pinfunction "VDD1_6_U3") (pintype "passive"))
      (node (ref "D12") (pin "U4") (pinfunction "VDD1_7_U4") (pintype "passive"))
      (node (ref "D12") (pin "U5") (pinfunction "VDD1_8_U5") (pintype "passive"))
      (node (ref "D12") (pin "U6") (pinfunction "VDD1_9_U6") (pintype "passive"))
    )
    (net (code "3") (name "/VCC_DDR") (class "Default")
      (node (ref "C201") (pin "1") (pinfunction "1_1") (pintype "power_in"))
      (node (ref "C202") (pin "1") (pinfunction "1_1") (pintype "power_in"))
      (node (ref "C213") (pin "1") (pinfunction "1_1") (pintype "power_in"))
      (node (ref "C214") (pin "1") (pinfunction "1_1") (pintype "power_in"))
      (node (ref "C215") (pin "1") (pinfunction "1_1") (pintype "power_in"))
      (node (ref "C216") (pin "1") (pinfunction "1_1") (pintype "power_in"))
      (node (ref "C217") (pin "1") (pinfunction "1_1") (pintype "power_in"))
      (node (ref "C218") (pin "1") (pinfunction "1_1") (pintype "power_in"))
      (node (ref "C219") (pin "1") (pinfunction "1_1") (pintype "power_in"))
      (node (ref "C220") (pin "2") (pinfunction "2_2") (pintype "power_in"))
      (node (ref "C232") (pin "1") (pinfunction "1_1") (pintype "power_in"))
      (node (ref "C233") (pin "1") (pinfunction "1_1") (pintype "power_in"))
      (node (ref "C234") (pin "1") (pinfunction "1_1") (pintype "power_in"))
      (node (ref "C235") (pin "1") (pinfunction "1_1") (pintype "power_in"))
      (node (ref "C236") (pin "1") (pinfunction "1_1") (pintype "power_in"))
      (node (ref "C237") (pin "1") (pinfunction "1_1") (pintype "power_in"))
      (node (ref "C238") (pin "1") (pinfunction "1_1") (pintype "power_in"))
      (node (ref "C239") (pin "2") (pinfunction "2_2") (pintype "power_in"))
      (node (ref "C240") (pin "1") (pinfunction "1_1") (pintype "power_in"))
      (node (ref "C241") (pin "1") (pinfunction "1_1") (pintype "power_in"))
      (node (ref "C242") (pin "1") (pinfunction "1_1") (pintype "power_in"))
      (node (ref "C243") (pin "1") (pinfunction "1_1") (pintype "power_in"))
      (node (ref "C244") (pin "1") (pinfunction "1_1") (pintype "power_in"))
      (node (ref "C245") (pin "1") (pinfunction "1_1") (pintype "power_in"))
      (node (ref "C246") (pin "1") (pinfunction "1_1") (pintype "power_in"))
      (node (ref "C247") (pin "2") (pinfunction "2_2") (pintype "power_in"))
      (node (ref "C248") (pin "1") (pinfunction "1_1") (pintype "power_in"))
      (node (ref "C249") (pin "1") (pinfunction "1_1") (pintype "power_in"))
      (node (ref "C250") (pin "1") (pinfunction "1_1") (pintype "power_in"))
      (node (ref "C251") (pin "1") (pinfunction "1_1") (pintype "power_in"))
      (node (ref "C252") (pin "1") (pinfunction "1_1") (pintype "power_in"))
      (node (ref "C253") (pin "1") (pinfunction "1_1") (pintype "power_in"))
      (node (ref "C254") (pin "1") (pinfunction "1_1") (pintype "power_in"))
      (node (ref "C255") (pin "2") (pinfunction "2_2") (pintype "power_in"))
      (node (ref "D11") (pin "A11") (pinfunction "VDDQ_17_A11") (pintype "passive"))
      (node (ref "D11") (pin "A8") (pinfunction "VDD2_20_A8") (pintype "passive"))
      (node (ref "D11") (pin "A9") (pinfunction "VDD2_19_A9") (pintype "passive"))
      (node (ref "D11") (pin "C12") (pinfunction "VDDQ_16_C12") (pintype "passive"))
      (node (ref "D11") (pin "D4") (pinfunction "VDD2_18_D4") (pintype "passive"))
      (node (ref "D11") (pin "D5") (pinfunction "VDD2_17_D5") (pintype "passive"))
      (node (ref "D11") (pin "D6") (pinfunction "VDD2_16_D6") (pintype "passive"))
      (node (ref "D11") (pin "E12") (pinfunction "VDDQ_14_E12") (pintype "passive"))
      (node (ref "D11") (pin "E8") (pinfunction "VDDQ_15_E8") (pintype "passive"))
      (node (ref "D11") (pin "F2") (pinfunction "VDDCA5_F2") (pintype "passive"))
      (node (ref "D11") (pin "G12") (pinfunction "VDDQ_13_G12") (pintype "passive"))
      (node (ref "D11") (pin "G2") (pinfunction "VDDCA4_G2") (pintype "passive"))
      (node (ref "D11") (pin "G5") (pinfunction "VDD2_15_G5") (pintype "passive"))
      (node (ref "D11") (pin "H11") (pinfunction "VDDQ_10_H11") (pintype "passive"))
      (node (ref "D11") (pin "H12") (pinfunction "VDD2_12_H12") (pintype "passive"))
      (node (ref "D11") (pin "H3") (pinfunction "VDDCA3_H3") (pintype "passive"))
      (node (ref "D11") (pin "H5") (pinfunction "VDD2_14_H5") (pintype "passive"))
      (node (ref "D11") (pin "H6") (pinfunction "VDD2_13_H6") (pintype "passive"))
      (node (ref "D11") (pin "H8") (pinfunction "VDDQ_12_H8") (pintype "passive"))
      (node (ref "D11") (pin "H9") (pinfunction "VDDQ_11_H9") (pintype "passive"))
      (node (ref "D11") (pin "J10") (pinfunction "VDDQ_8_J10") (pintype "passive"))
      (node (ref "D11") (pin "J5") (pinfunction "VDD2_11_J5") (pintype "passive"))
      (node (ref "D11") (pin "J6") (pinfunction "VDD2_10_J6") (pintype "passive"))
      (node (ref "D11") (pin "J9") (pinfunction "VDDQ_9_J9") (pintype "passive"))
      (node (ref "D11") (pin "K11") (pinfunction "VDDQ_6_K11") (pintype "passive"))
      (node (ref "D11") (pin "K12") (pinfunction "VDD2_7_K12") (pintype "passive"))
      (node (ref "D11") (pin "K5") (pinfunction "VDD2_9_K5") (pintype "passive"))
      (node (ref "D11") (pin "K6") (pinfunction "VDD2_8_K6") (pintype "passive"))
      (node (ref "D11") (pin "K8") (pinfunction "VDDQ_7_K8") (pintype "passive"))
      (node (ref "D11") (pin "L12") (pinfunction "VDDQ_5_L12") (pintype "passive"))
      (node (ref "D11") (pin "L2") (pinfunction "VDDCA2_L2") (pintype "passive"))
      (node (ref "D11") (pin "L5") (pinfunction "VDD2_6_L5") (pintype "passive"))
      (node (ref "D11") (pin "M2") (pinfunction "VDDCA1_M2") (pintype "passive"))
      (node (ref "D11") (pin "N12") (pinfunction "VDDQ_3_N12") (pintype "passive"))
      (node (ref "D11") (pin "N8") (pinfunction "VDDQ_4_N8") (pintype "passive"))
      (node (ref "D11") (pin "P4") (pinfunction "VDD2_5_P4") (pintype "passive"))
      (node (ref "D11") (pin "P5") (pinfunction "VDD2_4_P5") (pintype "passive"))
      (node (ref "D11") (pin "P6") (pinfunction "VDD2_3_P6") (pintype "passive"))
      (node (ref "D11") (pin "R12") (pinfunction "VDDQ_2_R12") (pintype "passive"))
      (node (ref "D11") (pin "U11") (pinfunction "VDDQ_1_U11") (pintype "passive"))
      (node (ref "D11") (pin "U8") (pinfunction "VDD2_2_U8") (pintype "passive"))
      (node (ref "D11") (pin "U9") (pinfunction "VDD2_1_U9") (pintype "passive"))
      (node (ref "D12") (pin "A11") (pinfunction "VDDQ_17_A11") (pintype "passive"))
      (node (ref "D12") (pin "A8") (pinfunction "VDD2_20_A8") (pintype "passive"))
      (node (ref "D12") (pin "A9") (pinfunction "VDD2_19_A9") (pintype "passive"))
      (node (ref "D12") (pin "C12") (pinfunction "VDDQ_16_C12") (pintype "passive"))
      (node (ref "D12") (pin "D4") (pinfunction "VDD2_18_D4") (pintype "passive"))
      (node (ref "D12") (pin "D5") (pinfunction "VDD2_17_D5") (pintype "passive"))
      (node (ref "D12") (pin "D6") (pinfunction "VDD2_16_D6") (pintype "passive"))
      (node (ref "D12") (pin "E12") (pinfunction "VDDQ_14_E12") (pintype "passive"))
      (node (ref "D12") (pin "E8") (pinfunction "VDDQ_15_E8") (pintype "passive"))
      (node (ref "D12") (pin "F2") (pinfunction "VDDCA5_F2") (pintype "passive"))
      (node (ref "D12") (pin "G12") (pinfunction "VDDQ_13_G12") (pintype "passive"))
      (node (ref "D12") (pin "G2") (pinfunction "VDDCA4_G2") (pintype "passive"))
      (node (ref "D12") (pin "G5") (pinfunction "VDD2_15_G5") (pintype "passive"))
      (node (ref "D12") (pin "H11") (pinfunction "VDDQ_10_H11") (pintype "passive"))
      (node (ref "D12") (pin "H12") (pinfunction "VDD2_12_H12") (pintype "passive"))
      (node (ref "D12") (pin "H3") (pinfunction "VDDCA3_H3") (pintype "passive"))
      (node (ref "D12") (pin "H5") (pinfunction "VDD2_14_H5") (pintype "passive"))
      (node (ref "D12") (pin "H6") (pinfunction "VDD2_13_H6") (pintype "passive"))
      (node (ref "D12") (pin "H8") (pinfunction "VDDQ_12_H8") (pintype "passive"))
      (node (ref "D12") (pin "H9") (pinfunction "VDDQ_11_H9") (pintype "passive"))
      (node (ref "D12") (pin "J10") (pinfunction "VDDQ_8_J10") (pintype "passive"))
      (node (ref "D12") (pin "J5") (pinfunction "VDD2_11_J5") (pintype "passive"))
      (node (ref "D12") (pin "J6") (pinfunction "VDD2_10_J6") (pintype "passive"))
      (node (ref "D12") (pin "J9") (pinfunction "VDDQ_9_J9") (pintype "passive"))
      (node (ref "D12") (pin "K11") (pinfunction "VDDQ_6_K11") (pintype "passive"))
      (node (ref "D12") (pin "K12") (pinfunction "VDD2_7_K12") (pintype "passive"))
      (node (ref "D12") (pin "K5") (pinfunction "VDD2_9_K5") (pintype "passive"))
      (node (ref "D12") (pin "K6") (pinfunction "VDD2_8_K6") (pintype "passive"))
      (node (ref "D12") (pin "K8") (pinfunction "VDDQ_7_K8") (pintype "passive"))
      (node (ref "D12") (pin "L12") (pinfunction "VDDQ_5_L12") (pintype "passive"))
      (node (ref "D12") (pin "L2") (pinfunction "VDDCA2_L2") (pintype "passive"))
      (node (ref "D12") (pin "L5") (pinfunction "VDD2_6_L5") (pintype "passive"))
      (node (ref "D12") (pin "M2") (pinfunction "VDDCA1_M2") (pintype "passive"))
      (node (ref "D12") (pin "N12") (pinfunction "VDDQ_3_N12") (pintype "passive"))
      (node (ref "D12") (pin "N8") (pinfunction "VDDQ_4_N8") (pintype "passive"))
      (node (ref "D12") (pin "P4") (pinfunction "VDD2_5_P4") (pintype "passive"))
      (node (ref "D12") (pin "P5") (pinfunction "VDD2_4_P5") (pintype "passive"))
      (node (ref "D12") (pin "P6") (pinfunction "VDD2_3_P6") (pintype "passive"))
      (node (ref "D12") (pin "R12") (pinfunction "VDDQ_2_R12") (pintype "passive"))
      (node (ref "D12") (pin "U11") (pinfunction "VDDQ_1_U11") (pintype "passive"))
      (node (ref "D12") (pin "U8") (pinfunction "VDD2_2_U8") (pintype "passive"))
      (node (ref "D12") (pin "U9") (pinfunction "VDD2_1_U9") (pintype "passive"))
      (node (ref "R59") (pin "2") (pinfunction "2_2") (pintype "passive"))
      (node (ref "R60") (pin "2") (pinfunction "2_2") (pintype "passive"))
      (node (ref "R63") (pin "2") (pinfunction "2_2") (pintype "passive"))
      (node (ref "R64") (pin "2") (pinfunction "2_2") (pintype "passive"))
    )
    (net (code "4") (name "/VREFCA_DDR0") (class "Default")
      (node (ref "C202") (pin "2") (pinfunction "2_2") (pintype "power_in"))
      (node (ref "C206") (pin "1") (pinfunction "1_1") (pintype "power_in"))
      (node (ref "C207") (pin "2") (pinfunction "2_2") (pintype "power_in"))
      (node (ref "C208") (pin "2") (pinfunction "2_2") (pintype "power_in"))
      (node (ref "D11") (pin "H4") (pinfunction "DDR_VREFCA_H4") (pintype "passive"))
      (node (ref "R60") (pin "1") (pinfunction "1_1") (pintype "passive"))
      (node (ref "R62") (pin "2") (pinfunction "2_2") (pintype "passive"))
    )
    (net (code "5") (name "/VREFCA_DDR1") (class "Default")
      (node (ref "C201") (pin "2") (pinfunction "2_2") (pintype "power_in"))
      (node (ref "C203") (pin "1") (pinfunction "1_1") (pintype "power_in"))
      (node (ref "C204") (pin "2") (pinfunction "2_2") (pintype "power_in"))
      (node (ref "C205") (pin "2") (pinfunction "2_2") (pintype "power_in"))
      (node (ref "D12") (pin "H4") (pinfunction "DDR_VREFCA_H4") (pintype "passive"))
      (node (ref "R59") (pin "1") (pinfunction "1_1") (pintype "passive"))
      (node (ref "R61") (pin "2") (pinfunction "2_2") (pintype "passive"))
    )
    (net (code "6") (name "/VREFDQ_DDR0") (class "Default")
      (node (ref "C211") (pin "2") (pinfunction "2_2") (pintype "power_in"))
      (node (ref "C212") (pin "2") (pinfunction "2_2") (pintype "power_in"))
      (node (ref "D11") (pin "J11") (pinfunction "DDR_VREFDQ_J11") (pintype "passive"))
      (node (ref "R64") (pin "1") (pinfunction "1_1") (pintype "passive"))
      (node (ref "R66") (pin "2") (pinfunction "2_2") (pintype "passive"))
    )
    (net (code "7") (name "/VREFDQ_DDR1") (class "Default")
      (node (ref "C209") (pin "2") (pinfunction "2_2") (pintype "power_in"))
      (node (ref "C210") (pin "2") (pinfunction "2_2") (pintype "power_in"))
      (node (ref "D12") (pin "J11") (pinfunction "DDR_VREFDQ_J11") (pintype "passive"))
      (node (ref "R63") (pin "1") (pinfunction "1_1") (pintype "passive"))
      (node (ref "R65") (pin "2") (pinfunction "2_2") (pintype "passive"))
    )
    (net (code "8") (name "unconnected-(D11B-NC1-PadC4)") (class "Default")
      (node (ref "D11") (pin "C4") (pinfunction "NC1_C4") (pintype "passive"))
    )
    (net (code "9") (name "unconnected-(D11B-NC2-PadK9)") (class "Default")
      (node (ref "D11") (pin "K9") (pinfunction "NC2_K9") (pintype "passive"))
    )
    (net (code "10") (name "unconnected-(D11B-NC3-PadR3)") (class "Default")
      (node (ref "D11") (pin "R3") (pinfunction "NC3_R3") (pintype "passive"))
    )
    (net (code "11") (name "unconnected-(D12B-NC1-PadC4)") (class "Default")
      (node (ref "D12") (pin "C4") (pinfunction "NC1_C4") (pintype "passive"))
    )
    (net (code "12") (name "unconnected-(D12B-NC2-PadK9)") (class "Default")
      (node (ref "D12") (pin "K9") (pinfunction "NC2_K9") (pintype "passive"))
    )
    (net (code "13") (name "unconnected-(D12B-NC3-PadR3)") (class "Default")
      (node (ref "D12") (pin "R3") (pinfunction "NC3_R3") (pintype "passive"))
    )
  )
)
